# arduino_proto_2.net
KiCad netlist of a schematic drawn in EAGLE
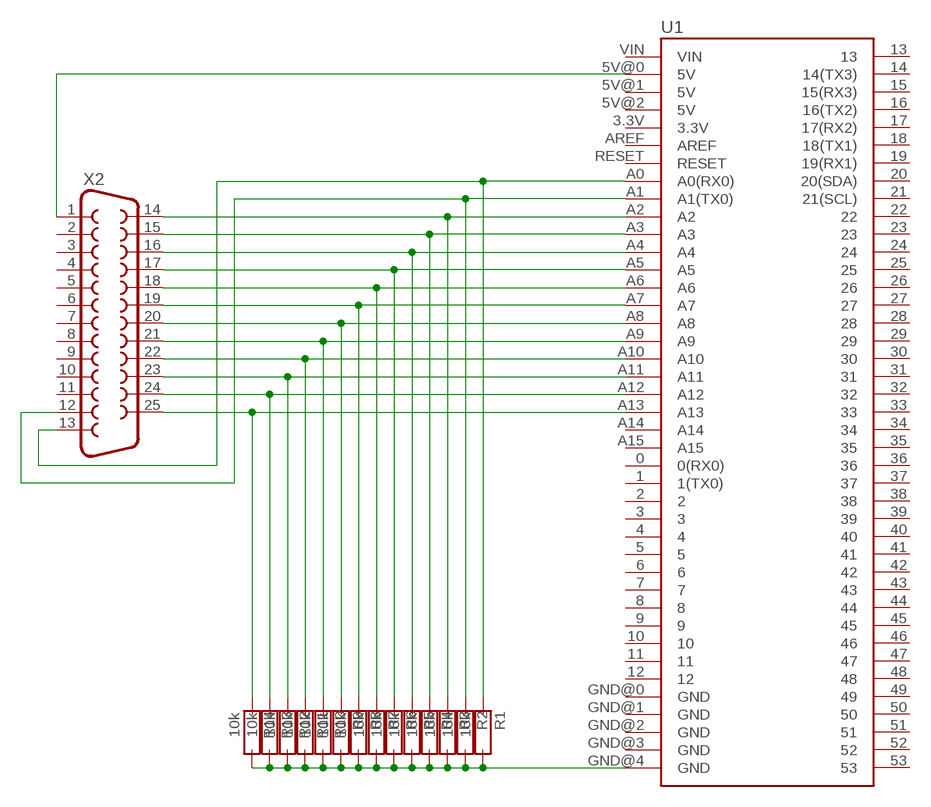
[diagram p0: schematic, sheet 1]

(export (version "E")
  (design (tool "Eeschema 10.0.6"))
  (components
    (comp (ref "R1")
      (value "10k")
      (footprint "eagle-import:AX3")
      (libsource (lib "eagle-import") (part "R3"))
    )
    (comp (ref "R2")
      (value "10k")
      (footprint "eagle-import:AX3")
      (libsource (lib "eagle-import") (part "R3"))
    )
    (comp (ref "R3")
      (value "10k")
      (footprint "eagle-import:AX3")
      (libsource (lib "eagle-import") (part "R3"))
    )
    (comp (ref "R4")
      (value "10k")
      (footprint "eagle-import:AX3")
      (libsource (lib "eagle-import") (part "R3"))
    )
    (comp (ref "R5")
      (value "10k")
      (footprint "eagle-import:AX3")
      (libsource (lib "eagle-import") (part "R3"))
    )
    (comp (ref "R6")
      (value "10k")
      (footprint "eagle-import:AX3")
      (libsource (lib "eagle-import") (part "R3"))
    )
    (comp (ref "R7")
      (value "10k")
      (footprint "eagle-import:AX3")
      (libsource (lib "eagle-import") (part "R3"))
    )
    (comp (ref "R8")
      (value "10k")
      (footprint "eagle-import:AX3")
      (libsource (lib "eagle-import") (part "R3"))
    )
    (comp (ref "R9")
      (value "10k")
      (footprint "eagle-import:AX3")
      (libsource (lib "eagle-import") (part "R3"))
    )
    (comp (ref "R10")
      (value "10k")
      (footprint "eagle-import:AX3")
      (libsource (lib "eagle-import") (part "R3"))
    )
    (comp (ref "R11")
      (value "10k")
      (footprint "eagle-import:AX3")
      (libsource (lib "eagle-import") (part "R3"))
    )
    (comp (ref "R12")
      (value "10k")
      (footprint "eagle-import:AX3")
      (libsource (lib "eagle-import") (part "R3"))
    )
    (comp (ref "R13")
      (value "10k")
      (footprint "eagle-import:AX3")
      (libsource (lib "eagle-import") (part "R3"))
    )
    (comp (ref "R14")
      (value "10k")
      (footprint "eagle-import:AX3")
      (libsource (lib "eagle-import") (part "R3"))
    )
    (comp (ref "U1")
      (value "ARDUINO-MEGAFULL")
      (footprint "eagle-import:ARDUINO_MEGA")
      (libsource (lib "eagle-import") (part "ARDUINO-MEGAFULL"))
    )
    (comp (ref "X2")
      (value "F25HP")
      (footprint "eagle-import:F25HP")
      (libsource (lib "eagle-import") (part "F25HP"))
    )
  )
  (nets
    (net (code "1") (name "Net-(R1-Pad2)") (class "Default")
      (node (ref "R1") (pin "2") (pinfunction "2_2") (pintype "passive"))
      (node (ref "R10") (pin "2") (pinfunction "2_2") (pintype "passive"))
      (node (ref "R11") (pin "2") (pinfunction "2_2") (pintype "passive"))
      (node (ref "R12") (pin "2") (pinfunction "2_2") (pintype "passive"))
      (node (ref "R13") (pin "2") (pinfunction "2_2") (pintype "passive"))
      (node (ref "R14") (pin "2") (pinfunction "2_2") (pintype "passive"))
      (node (ref "R2") (pin "2") (pinfunction "2_2") (pintype "passive"))
      (node (ref "R3") (pin "2") (pinfunction "2_2") (pintype "passive"))
      (node (ref "R4") (pin "2") (pinfunction "2_2") (pintype "passive"))
      (node (ref "R5") (pin "2") (pinfunction "2_2") (pintype "passive"))
      (node (ref "R6") (pin "2") (pinfunction "2_2") (pintype "passive"))
      (node (ref "R7") (pin "2") (pinfunction "2_2") (pintype "passive"))
      (node (ref "R8") (pin "2") (pinfunction "2_2") (pintype "passive"))
      (node (ref "R9") (pin "2") (pinfunction "2_2") (pintype "passive"))
      (node (ref "U1") (pin "GND@4") (pinfunction "GND_GND@4") (pintype "bidirectional"))
    )
    (net (code "2") (name "Net-(R3-Pad1)") (class "Default")
      (node (ref "R3") (pin "1") (pinfunction "1_1") (pintype "passive"))
      (node (ref "U1") (pin "A2") (pinfunction "A2_A2") (pintype "bidirectional"))
      (node (ref "X2") (pin "14") (pinfunction "14_14") (pintype "passive"))
    )
    (net (code "3") (name "Net-(R4-Pad1)") (class "Default")
      (node (ref "R4") (pin "1") (pinfunction "1_1") (pintype "passive"))
      (node (ref "U1") (pin "A3") (pinfunction "A3_A3") (pintype "bidirectional"))
      (node (ref "X2") (pin "15") (pinfunction "15_15") (pintype "passive"))
    )
    (net (code "4") (name "Net-(R5-Pad1)") (class "Default")
      (node (ref "R5") (pin "1") (pinfunction "1_1") (pintype "passive"))
      (node (ref "U1") (pin "A4") (pinfunction "A4_A4") (pintype "bidirectional"))
      (node (ref "X2") (pin "16") (pinfunction "16_16") (pintype "passive"))
    )
    (net (code "5") (name "Net-(R6-Pad1)") (class "Default")
      (node (ref "R6") (pin "1") (pinfunction "1_1") (pintype "passive"))
      (node (ref "U1") (pin "A5") (pinfunction "A5_A5") (pintype "bidirectional"))
      (node (ref "X2") (pin "17") (pinfunction "17_17") (pintype "passive"))
    )
    (net (code "6") (name "Net-(R7-Pad1)") (class "Default")
      (node (ref "R7") (pin "1") (pinfunction "1_1") (pintype "passive"))
      (node (ref "U1") (pin "A6") (pinfunction "A6_A6") (pintype "bidirectional"))
      (node (ref "X2") (pin "18") (pinfunction "18_18") (pintype "passive"))
    )
    (net (code "7") (name "Net-(R8-Pad1)") (class "Default")
      (node (ref "R8") (pin "1") (pinfunction "1_1") (pintype "passive"))
      (node (ref "U1") (pin "A7") (pinfunction "A7_A7") (pintype "bidirectional"))
      (node (ref "X2") (pin "19") (pinfunction "19_19") (pintype "passive"))
    )
    (net (code "8") (name "Net-(R9-Pad1)") (class "Default")
      (node (ref "R9") (pin "1") (pinfunction "1_1") (pintype "passive"))
      (node (ref "U1") (pin "A8") (pinfunction "A8_A8") (pintype "bidirectional"))
      (node (ref "X2") (pin "20") (pinfunction "20_20") (pintype "passive"))
    )
    (net (code "9") (name "Net-(R10-Pad1)") (class "Default")
      (node (ref "R10") (pin "1") (pinfunction "1_1") (pintype "passive"))
      (node (ref "U1") (pin "A9") (pinfunction "A9_A9") (pintype "bidirectional"))
      (node (ref "X2") (pin "21") (pinfunction "21_21") (pintype "passive"))
    )
    (net (code "10") (name "Net-(R11-Pad1)") (class "Default")
      (node (ref "R11") (pin "1") (pinfunction "1_1") (pintype "passive"))
      (node (ref "U1") (pin "A10") (pinfunction "A10_A10") (pintype "bidirectional"))
      (node (ref "X2") (pin "22") (pinfunction "22_22") (pintype "passive"))
    )
    (net (code "11") (name "Net-(R12-Pad1)") (class "Default")
      (node (ref "R12") (pin "1") (pinfunction "1_1") (pintype "passive"))
      (node (ref "U1") (pin "A11") (pinfunction "A11_A11") (pintype "bidirectional"))
      (node (ref "X2") (pin "23") (pinfunction "23_23") (pintype "passive"))
    )
    (net (code "12") (name "Net-(R13-Pad1)") (class "Default")
      (node (ref "R13") (pin "1") (pinfunction "1_1") (pintype "passive"))
      (node (ref "U1") (pin "A12") (pinfunction "A12_A12") (pintype "bidirectional"))
      (node (ref "X2") (pin "24") (pinfunction "24_24") (pintype "passive"))
    )
    (net (code "13") (name "Net-(R14-Pad1)") (class "Default")
      (node (ref "R14") (pin "1") (pinfunction "1_1") (pintype "passive"))
      (node (ref "U1") (pin "A13") (pinfunction "A13_A13") (pintype "bidirectional"))
      (node (ref "X2") (pin "25") (pinfunction "25_25") (pintype "passive"))
    )
    (net (code "14") (name "Net-(U1-5V-Pad5V@0)") (class "Default")
      (node (ref "U1") (pin "5V@0") (pinfunction "5V_5V@0") (pintype "bidirectional"))
      (node (ref "X2") (pin "1") (pinfunction "1_1") (pintype "passive"))
    )
    (net (code "15") (name "Net-(U1-A0(RX0))") (class "Default")
      (node (ref "R1") (pin "1") (pinfunction "1_1") (pintype "passive"))
      (node (ref "U1") (pin "A0") (pinfunction "A0(RX0)_A0") (pintype "bidirectional"))
      (node (ref "X2") (pin "13") (pinfunction "13_13") (pintype "passive"))
    )
    (net (code "16") (name "Net-(U1-A1(TX0))") (class "Default")
      (node (ref "R2") (pin "1") (pinfunction "1_1") (pintype "passive"))
      (node (ref "U1") (pin "A1") (pinfunction "A1(TX0)_A1") (pintype "bidirectional"))
      (node (ref "X2") (pin "12") (pinfunction "12_12") (pintype "passive"))
    )
    (net (code "17") (name "unconnected-(U1-0(RX0)-Pad0)") (class "Default")
      (node (ref "U1") (pin "0") (pinfunction "0(RX0)_0") (pintype "bidirectional"))
    )
    (net (code "18") (name "unconnected-(U1-1(TX0)-Pad1)") (class "Default")
      (node (ref "U1") (pin "1") (pinfunction "1(TX0)_1") (pintype "bidirectional"))
    )
    (net (code "19") (name "unconnected-(U1-5V-Pad5V@1)") (class "Default")
      (node (ref "U1") (pin "5V@1") (pinfunction "5V_5V@1") (pintype "bidirectional"))
    )
    (net (code "20") (name "unconnected-(U1-5V-Pad5V@2)") (class "Default")
      (node (ref "U1") (pin "5V@2") (pinfunction "5V_5V@2") (pintype "bidirectional"))
    )
    (net (code "21") (name "unconnected-(U1-14(TX3)-Pad14)") (class "Default")
      (node (ref "U1") (pin "14") (pinfunction "14(TX3)_14") (pintype "bidirectional"))
    )
    (net (code "22") (name "unconnected-(U1-15(RX3)-Pad15)") (class "Default")
      (node (ref "U1") (pin "15") (pinfunction "15(RX3)_15") (pintype "bidirectional"))
    )
    (net (code "23") (name "unconnected-(U1-16(TX2)-Pad16)") (class "Default")
      (node (ref "U1") (pin "16") (pinfunction "16(TX2)_16") (pintype "bidirectional"))
    )
    (net (code "24") (name "unconnected-(U1-17(RX2)-Pad17)") (class "Default")
      (node (ref "U1") (pin "17") (pinfunction "17(RX2)_17") (pintype "bidirectional"))
    )
    (net (code "25") (name "unconnected-(U1-18(TX1)-Pad18)") (class "Default")
      (node (ref "U1") (pin "18") (pinfunction "18(TX1)_18") (pintype "bidirectional"))
    )
    (net (code "26") (name "unconnected-(U1-19(RX1)-Pad19)") (class "Default")
      (node (ref "U1") (pin "19") (pinfunction "19(RX1)_19") (pintype "bidirectional"))
    )
    (net (code "27") (name "unconnected-(U1-20(SDA)-Pad20)") (class "Default")
      (node (ref "U1") (pin "20") (pinfunction "20(SDA)_20") (pintype "bidirectional"))
    )
    (net (code "28") (name "unconnected-(U1-21(SCL)-Pad21)") (class "Default")
      (node (ref "U1") (pin "21") (pinfunction "21(SCL)_21") (pintype "bidirectional"))
    )
    (net (code "29") (name "unconnected-(U1-GND-PadGND@0)") (class "Default")
      (node (ref "U1") (pin "GND@0") (pinfunction "GND_GND@0") (pintype "bidirectional"))
    )
    (net (code "30") (name "unconnected-(U1-GND-PadGND@1)") (class "Default")
      (node (ref "U1") (pin "GND@1") (pinfunction "GND_GND@1") (pintype "bidirectional"))
    )
    (net (code "31") (name "unconnected-(U1-GND-PadGND@2)") (class "Default")
      (node (ref "U1") (pin "GND@2") (pinfunction "GND_GND@2") (pintype "bidirectional"))
    )
    (net (code "32") (name "unconnected-(U1-GND-PadGND@3)") (class "Default")
      (node (ref "U1") (pin "GND@3") (pinfunction "GND_GND@3") (pintype "bidirectional"))
    )
    (net (code "33") (name "unconnected-(U1-Pad2)") (class "Default")
      (node (ref "U1") (pin "2") (pinfunction "2_2") (pintype "bidirectional"))
    )
    (net (code "34") (name "unconnected-(U1-Pad3)") (class "Default")
      (node (ref "U1") (pin "3") (pinfunction "3_3") (pintype "bidirectional"))
    )
    (net (code "35") (name "unconnected-(U1-Pad3.3V)") (class "Default")
      (node (ref "U1") (pin "3.3V") (pinfunction "3.3V_3.3V") (pintype "bidirectional"))
    )
    (net (code "36") (name "unconnected-(U1-Pad4)") (class "Default")
      (node (ref "U1") (pin "4") (pinfunction "4_4") (pintype "bidirectional"))
    )
    (net (code "37") (name "unconnected-(U1-Pad5)") (class "Default")
      (node (ref "U1") (pin "5") (pinfunction "5_5") (pintype "bidirectional"))
    )
    (net (code "38") (name "unconnected-(U1-Pad6)") (class "Default")
      (node (ref "U1") (pin "6") (pinfunction "6_6") (pintype "bidirectional"))
    )
    (net (code "39") (name "unconnected-(U1-Pad7)") (class "Default")
      (node (ref "U1") (pin "7") (pinfunction "7_7") (pintype "bidirectional"))
    )
    (net (code "40") (name "unconnected-(U1-Pad8)") (class "Default")
      (node (ref "U1") (pin "8") (pinfunction "8_8") (pintype "bidirectional"))
    )
    (net (code "41") (name "unconnected-(U1-Pad9)") (class "Default")
      (node (ref "U1") (pin "9") (pinfunction "9_9") (pintype "bidirectional"))
    )
    (net (code "42") (name "unconnected-(U1-Pad10)") (class "Default")
      (node (ref "U1") (pin "10") (pinfunction "10_10") (pintype "bidirectional"))
    )
    (net (code "43") (name "unconnected-(U1-Pad11)") (class "Default")
      (node (ref "U1") (pin "11") (pinfunction "11_11") (pintype "bidirectional"))
    )
    (net (code "44") (name "unconnected-(U1-Pad12)") (class "Default")
      (node (ref "U1") (pin "12") (pinfunction "12_12") (pintype "bidirectional"))
    )
    (net (code "45") (name "unconnected-(U1-Pad13)") (class "Default")
      (node (ref "U1") (pin "13") (pinfunction "13_13") (pintype "bidirectional"))
    )
    (net (code "46") (name "unconnected-(U1-Pad22)") (class "Default")
      (node (ref "U1") (pin "22") (pinfunction "22_22") (pintype "bidirectional"))
    )
    (net (code "47") (name "unconnected-(U1-Pad23)") (class "Default")
      (node (ref "U1") (pin "23") (pinfunction "23_23") (pintype "bidirectional"))
    )
    (net (code "48") (name "unconnected-(U1-Pad24)") (class "Default")
      (node (ref "U1") (pin "24") (pinfunction "24_24") (pintype "bidirectional"))
    )
    (net (code "49") (name "unconnected-(U1-Pad25)") (class "Default")
      (node (ref "U1") (pin "25") (pinfunction "25_25") (pintype "bidirectional"))
    )
    (net (code "50") (name "unconnected-(U1-Pad26)") (class "Default")
      (node (ref "U1") (pin "26") (pinfunction "26_26") (pintype "bidirectional"))
    )
    (net (code "51") (name "unconnected-(U1-Pad27)") (class "Default")
      (node (ref "U1") (pin "27") (pinfunction "27_27") (pintype "bidirectional"))
    )
    (net (code "52") (name "unconnected-(U1-Pad28)") (class "Default")
      (node (ref "U1") (pin "28") (pinfunction "28_28") (pintype "bidirectional"))
    )
    (net (code "53") (name "unconnected-(U1-Pad29)") (class "Default")
      (node (ref "U1") (pin "29") (pinfunction "29_29") (pintype "bidirectional"))
    )
    (net (code "54") (name "unconnected-(U1-Pad30)") (class "Default")
      (node (ref "U1") (pin "30") (pinfunction "30_30") (pintype "bidirectional"))
    )
    (net (code "55") (name "unconnected-(U1-Pad31)") (class "Default")
      (node (ref "U1") (pin "31") (pinfunction "31_31") (pintype "bidirectional"))
    )
    (net (code "56") (name "unconnected-(U1-Pad32)") (class "Default")
      (node (ref "U1") (pin "32") (pinfunction "32_32") (pintype "bidirectional"))
    )
    (net (code "57") (name "unconnected-(U1-Pad33)") (class "Default")
      (node (ref "U1") (pin "33") (pinfunction "33_33") (pintype "bidirectional"))
    )
    (net (code "58") (name "unconnected-(U1-Pad34)") (class "Default")
      (node (ref "U1") (pin "34") (pinfunction "34_34") (pintype "bidirectional"))
    )
    (net (code "59") (name "unconnected-(U1-Pad35)") (class "Default")
      (node (ref "U1") (pin "35") (pinfunction "35_35") (pintype "bidirectional"))
    )
    (net (code "60") (name "unconnected-(U1-Pad36)") (class "Default")
      (node (ref "U1") (pin "36") (pinfunction "36_36") (pintype "bidirectional"))
    )
    (net (code "61") (name "unconnected-(U1-Pad37)") (class "Default")
      (node (ref "U1") (pin "37") (pinfunction "37_37") (pintype "bidirectional"))
    )
    (net (code "62") (name "unconnected-(U1-Pad38)") (class "Default")
      (node (ref "U1") (pin "38") (pinfunction "38_38") (pintype "bidirectional"))
    )
    (net (code "63") (name "unconnected-(U1-Pad39)") (class "Default")
      (node (ref "U1") (pin "39") (pinfunction "39_39") (pintype "bidirectional"))
    )
    (net (code "64") (name "unconnected-(U1-Pad40)") (class "Default")
      (node (ref "U1") (pin "40") (pinfunction "40_40") (pintype "bidirectional"))
    )
    (net (code "65") (name "unconnected-(U1-Pad41)") (class "Default")
      (node (ref "U1") (pin "41") (pinfunction "41_41") (pintype "bidirectional"))
    )
    (net (code "66") (name "unconnected-(U1-Pad42)") (class "Default")
      (node (ref "U1") (pin "42") (pinfunction "42_42") (pintype "bidirectional"))
    )
    (net (code "67") (name "unconnected-(U1-Pad43)") (class "Default")
      (node (ref "U1") (pin "43") (pinfunction "43_43") (pintype "bidirectional"))
    )
    (net (code "68") (name "unconnected-(U1-Pad44)") (class "Default")
      (node (ref "U1") (pin "44") (pinfunction "44_44") (pintype "bidirectional"))
    )
    (net (code "69") (name "unconnected-(U1-Pad45)") (class "Default")
      (node (ref "U1") (pin "45") (pinfunction "45_45") (pintype "bidirectional"))
    )
    (net (code "70") (name "unconnected-(U1-Pad46)") (class "Default")
      (node (ref "U1") (pin "46") (pinfunction "46_46") (pintype "bidirectional"))
    )
    (net (code "71") (name "unconnected-(U1-Pad47)") (class "Default")
      (node (ref "U1") (pin "47") (pinfunction "47_47") (pintype "bidirectional"))
    )
    (net (code "72") (name "unconnected-(U1-Pad48)") (class "Default")
      (node (ref "U1") (pin "48") (pinfunction "48_48") (pintype "bidirectional"))
    )
    (net (code "73") (name "unconnected-(U1-Pad49)") (class "Default")
      (node (ref "U1") (pin "49") (pinfunction "49_49") (pintype "bidirectional"))
    )
    (net (code "74") (name "unconnected-(U1-Pad50)") (class "Default")
      (node (ref "U1") (pin "50") (pinfunction "50_50") (pintype "bidirectional"))
    )
    (net (code "75") (name "unconnected-(U1-Pad51)") (class "Default")
      (node (ref "U1") (pin "51") (pinfunction "51_51") (pintype "bidirectional"))
    )
    (net (code "76") (name "unconnected-(U1-Pad52)") (class "Default")
      (node (ref "U1") (pin "52") (pinfunction "52_52") (pintype "bidirectional"))
    )
    (net (code "77") (name "unconnected-(U1-Pad53)") (class "Default")
      (node (ref "U1") (pin "53") (pinfunction "53_53") (pintype "bidirectional"))
    )
    (net (code "78") (name "unconnected-(U1-PadA14)") (class "Default")
      (node (ref "U1") (pin "A14") (pinfunction "A14_A14") (pintype "bidirectional"))
    )
    (net (code "79") (name "unconnected-(U1-PadA15)") (class "Default")
      (node (ref "U1") (pin "A15") (pinfunction "A15_A15") (pintype "bidirectional"))
    )
    (net (code "80") (name "unconnected-(U1-PadAREF)") (class "Default")
      (node (ref "U1") (pin "AREF") (pinfunction "AREF_AREF") (pintype "bidirectional"))
    )
    (net (code "81") (name "unconnected-(U1-PadRESET)") (class "Default")
      (node (ref "U1") (pin "RESET") (pinfunction "RESET_RESET") (pintype "bidirectional"))
    )
    (net (code "82") (name "unconnected-(U1-PadVIN)") (class "Default")
      (node (ref "U1") (pin "VIN") (pinfunction "VIN_VIN") (pintype "bidirectional"))
    )
    (net (code "83") (name "unconnected-(X2-Pad2)") (class "Default")
      (node (ref "X2") (pin "2") (pinfunction "2_2") (pintype "passive"))
    )
    (net (code "84") (name "unconnected-(X2-Pad3)") (class "Default")
      (node (ref "X2") (pin "3") (pinfunction "3_3") (pintype "passive"))
    )
    (net (code "85") (name "unconnected-(X2-Pad4)") (class "Default")
      (node (ref "X2") (pin "4") (pinfunction "4_4") (pintype "passive"))
    )
    (net (code "86") (name "unconnected-(X2-Pad5)") (class "Default")
      (node (ref "X2") (pin "5") (pinfunction "5_5") (pintype "passive"))
    )
    (net (code "87") (name "unconnected-(X2-Pad6)") (class "Default")
      (node (ref "X2") (pin "6") (pinfunction "6_6") (pintype "passive"))
    )
    (net (code "88") (name "unconnected-(X2-Pad7)") (class "Default")
      (node (ref "X2") (pin "7") (pinfunction "7_7") (pintype "passive"))
    )
    (net (code "89") (name "unconnected-(X2-Pad8)") (class "Default")
      (node (ref "X2") (pin "8") (pinfunction "8_8") (pintype "passive"))
    )
    (net (code "90") (name "unconnected-(X2-Pad9)") (class "Default")
      (node (ref "X2") (pin "9") (pinfunction "9_9") (pintype "passive"))
    )
    (net (code "91") (name "unconnected-(X2-Pad10)") (class "Default")
      (node (ref "X2") (pin "10") (pinfunction "10_10") (pintype "passive"))
    )
    (net (code "92") (name "unconnected-(X2-Pad11)") (class "Default")
      (node (ref "X2") (pin "11") (pinfunction "11_11") (pintype "passive"))
    )
  )
)
